# HeaterDongle.net
KiCad netlist of a schematic drawn in Altium Designer
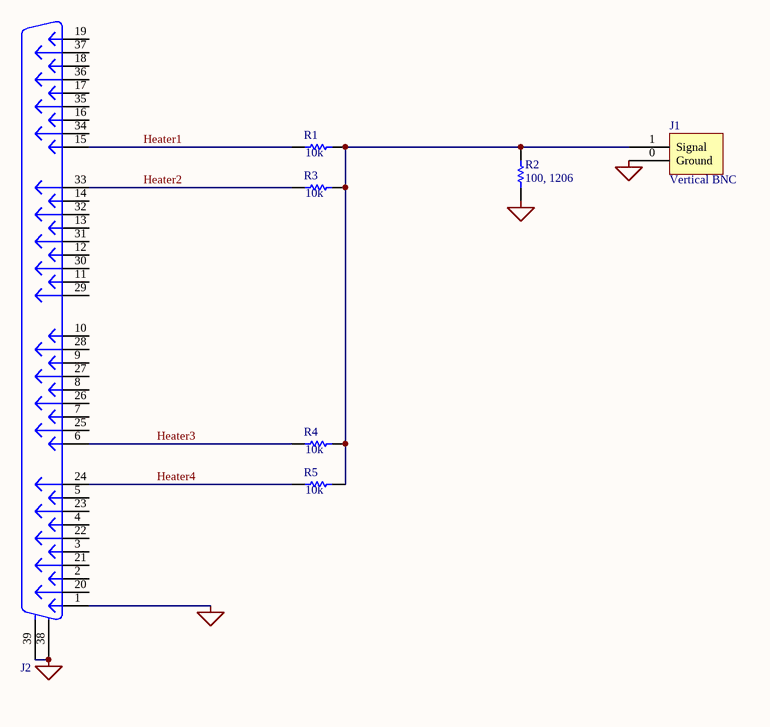
[diagram p0: HeaterDongle.SchDoc]

(export (version "E")
  (design (tool "Eeschema 10.0.6"))
  (components
    (comp (ref "J1")
      (value "Vertical BNC")
      (footprint "BNCVert")
      (libsource (lib "MGNGSQ4_Dongles") (part "BNCVertical"))
    )
    (comp (ref "J2")
      (value "DB37M")
      (footprint "DSUB37-M")
      (libsource (lib "MGNGSQ4_Dongles") (part "DB37M"))
    )
    (comp (ref "R1")
      (value "10k")
      (footprint "0603")
      (description "Resistor")
      (fields (field (name "TOLERANCE") "1%") (field (name "POWER") "1/10W"))
      (libsource (lib "MGNGSQ4_Dongles") (part "RES 0603"))
    )
    (comp (ref "R2")
      (value "100, 1206")
      (footprint "1206")
      (description "RES 100 OHM 1/4W 1206 SMD")
      (fields
        (field (name "MANUFACTURERS PART NUMBER") "ESR18EZPF1000")
        (field (name "MANUFACTURER") "Rohm Semiconductor")
      )
      (libsource (lib "MGNGSQ4_Dongles") (part "RES 1206"))
    )
    (comp (ref "R3")
      (value "10k")
      (footprint "0603")
      (description "Resistor")
      (fields (field (name "TOLERANCE") "1%") (field (name "POWER") "1/10W"))
      (libsource (lib "MGNGSQ4_Dongles") (part "RES 0603"))
    )
    (comp (ref "R4")
      (value "10k")
      (footprint "0603")
      (description "Resistor")
      (fields (field (name "TOLERANCE") "1%") (field (name "POWER") "1/10W"))
      (libsource (lib "MGNGSQ4_Dongles") (part "RES 0603"))
    )
    (comp (ref "R5")
      (value "10k")
      (footprint "0603")
      (description "Resistor")
      (fields (field (name "TOLERANCE") "1%") (field (name "POWER") "1/10W"))
      (libsource (lib "MGNGSQ4_Dongles") (part "RES 0603"))
    )
  )
  (nets
    (net (code "1") (name "/Heater1") (class "Default")
      (node (ref "J2") (pin "15") (pinfunction "15_15") (pintype "passive"))
      (node (ref "R1") (pin "1") (pinfunction "1_1") (pintype "passive"))
    )
    (net (code "2") (name "/Heater2") (class "Default")
      (node (ref "J2") (pin "33") (pinfunction "33_33") (pintype "passive"))
      (node (ref "R3") (pin "1") (pinfunction "1_1") (pintype "passive"))
    )
    (net (code "3") (name "/Heater3") (class "Default")
      (node (ref "J2") (pin "6") (pinfunction "6_6") (pintype "passive"))
      (node (ref "R4") (pin "1") (pinfunction "1_1") (pintype "passive"))
    )
    (net (code "4") (name "/Heater4") (class "Default")
      (node (ref "J2") (pin "24") (pinfunction "24_24") (pintype "passive"))
      (node (ref "R5") (pin "1") (pinfunction "1_1") (pintype "passive"))
    )
    (net (code "5") (name "GND") (class "Default")
      (node (ref "J1") (pin "0") (pinfunction "Ground_0") (pintype "passive"))
      (node (ref "J2") (pin "1") (pinfunction "1_1") (pintype "passive"))
      (node (ref "J2") (pin "38") (pinfunction "MH1_38") (pintype "passive"))
      (node (ref "J2") (pin "39") (pinfunction "MH2_39") (pintype "passive"))
      (node (ref "R2") (pin "1") (pinfunction "1_1") (pintype "passive"))
    )
    (net (code "6") (name "Net-(J1-Signal)") (class "Default")
      (node (ref "J1") (pin "1") (pinfunction "Signal_1") (pintype "passive"))
      (node (ref "R1") (pin "2") (pinfunction "2_2") (pintype "passive"))
      (node (ref "R2") (pin "2") (pinfunction "2_2") (pintype "passive"))
      (node (ref "R3") (pin "2") (pinfunction "2_2") (pintype "passive"))
      (node (ref "R4") (pin "2") (pinfunction "2_2") (pintype "passive"))
      (node (ref "R5") (pin "2") (pinfunction "2_2") (pintype "passive"))
    )
    (net (code "7") (name "unconnected-(J2-Pad2)") (class "Default")
      (node (ref "J2") (pin "2") (pinfunction "2_2") (pintype "passive"))
    )
    (net (code "8") (name "unconnected-(J2-Pad3)") (class "Default")
      (node (ref "J2") (pin "3") (pinfunction "3_3") (pintype "passive"))
    )
    (net (code "9") (name "unconnected-(J2-Pad4)") (class "Default")
      (node (ref "J2") (pin "4") (pinfunction "4_4") (pintype "passive"))
    )
    (net (code "10") (name "unconnected-(J2-Pad5)") (class "Default")
      (node (ref "J2") (pin "5") (pinfunction "5_5") (pintype "passive"))
    )
    (net (code "11") (name "unconnected-(J2-Pad7)") (class "Default")
      (node (ref "J2") (pin "7") (pinfunction "7_7") (pintype "passive"))
    )
    (net (code "12") (name "unconnected-(J2-Pad8)") (class "Default")
      (node (ref "J2") (pin "8") (pinfunction "8_8") (pintype "passive"))
    )
    (net (code "13") (name "unconnected-(J2-Pad9)") (class "Default")
      (node (ref "J2") (pin "9") (pinfunction "9_9") (pintype "passive"))
    )
    (net (code "14") (name "unconnected-(J2-Pad10)") (class "Default")
      (node (ref "J2") (pin "10") (pinfunction "10_10") (pintype "passive"))
    )
    (net (code "15") (name "unconnected-(J2-Pad11)") (class "Default")
      (node (ref "J2") (pin "11") (pinfunction "11_11") (pintype "passive"))
    )
    (net (code "16") (name "unconnected-(J2-Pad12)") (class "Default")
      (node (ref "J2") (pin "12") (pinfunction "12_12") (pintype "passive"))
    )
    (net (code "17") (name "unconnected-(J2-Pad13)") (class "Default")
      (node (ref "J2") (pin "13") (pinfunction "13_13") (pintype "passive"))
    )
    (net (code "18") (name "unconnected-(J2-Pad14)") (class "Default")
      (node (ref "J2") (pin "14") (pinfunction "14_14") (pintype "passive"))
    )
    (net (code "19") (name "unconnected-(J2-Pad16)") (class "Default")
      (node (ref "J2") (pin "16") (pinfunction "16_16") (pintype "passive"))
    )
    (net (code "20") (name "unconnected-(J2-Pad17)") (class "Default")
      (node (ref "J2") (pin "17") (pinfunction "17_17") (pintype "passive"))
    )
    (net (code "21") (name "unconnected-(J2-Pad18)") (class "Default")
      (node (ref "J2") (pin "18") (pinfunction "18_18") (pintype "passive"))
    )
    (net (code "22") (name "unconnected-(J2-Pad19)") (class "Default")
      (node (ref "J2") (pin "19") (pinfunction "19_19") (pintype "passive"))
    )
    (net (code "23") (name "unconnected-(J2-Pad20)") (class "Default")
      (node (ref "J2") (pin "20") (pinfunction "20_20") (pintype "passive"))
    )
    (net (code "24") (name "unconnected-(J2-Pad21)") (class "Default")
      (node (ref "J2") (pin "21") (pinfunction "21_21") (pintype "passive"))
    )
    (net (code "25") (name "unconnected-(J2-Pad22)") (class "Default")
      (node (ref "J2") (pin "22") (pinfunction "22_22") (pintype "passive"))
    )
    (net (code "26") (name "unconnected-(J2-Pad23)") (class "Default")
      (node (ref "J2") (pin "23") (pinfunction "23_23") (pintype "passive"))
    )
    (net (code "27") (name "unconnected-(J2-Pad25)") (class "Default")
      (node (ref "J2") (pin "25") (pinfunction "25_25") (pintype "passive"))
    )
    (net (code "28") (name "unconnected-(J2-Pad26)") (class "Default")
      (node (ref "J2") (pin "26") (pinfunction "26_26") (pintype "passive"))
    )
    (net (code "29") (name "unconnected-(J2-Pad27)") (class "Default")
      (node (ref "J2") (pin "27") (pinfunction "27_27") (pintype "passive"))
    )
    (net (code "30") (name "unconnected-(J2-Pad28)") (class "Default")
      (node (ref "J2") (pin "28") (pinfunction "28_28") (pintype "passive"))
    )
    (net (code "31") (name "unconnected-(J2-Pad29)") (class "Default")
      (node (ref "J2") (pin "29") (pinfunction "29_29") (pintype "passive"))
    )
    (net (code "32") (name "unconnected-(J2-Pad30)") (class "Default")
      (node (ref "J2") (pin "30") (pinfunction "30_30") (pintype "passive"))
    )
    (net (code "33") (name "unconnected-(J2-Pad31)") (class "Default")
      (node (ref "J2") (pin "31") (pinfunction "31_31") (pintype "passive"))
    )
    (net (code "34") (name "unconnected-(J2-Pad32)") (class "Default")
      (node (ref "J2") (pin "32") (pinfunction "32_32") (pintype "passive"))
    )
    (net (code "35") (name "unconnected-(J2-Pad34)") (class "Default")
      (node (ref "J2") (pin "34") (pinfunction "34_34") (pintype "passive"))
    )
    (net (code "36") (name "unconnected-(J2-Pad35)") (class "Default")
      (node (ref "J2") (pin "35") (pinfunction "35_35") (pintype "passive"))
    )
    (net (code "37") (name "unconnected-(J2-Pad36)") (class "Default")
      (node (ref "J2") (pin "36") (pinfunction "36_36") (pintype "passive"))
    )
    (net (code "38") (name "unconnected-(J2-Pad37)") (class "Default")
      (node (ref "J2") (pin "37") (pinfunction "37_37") (pintype "passive"))
    )
  )
)
